# SCH_G-Cacher_2026-07-07.net
KiCad netlist of a schematic drawn in EasyEDA
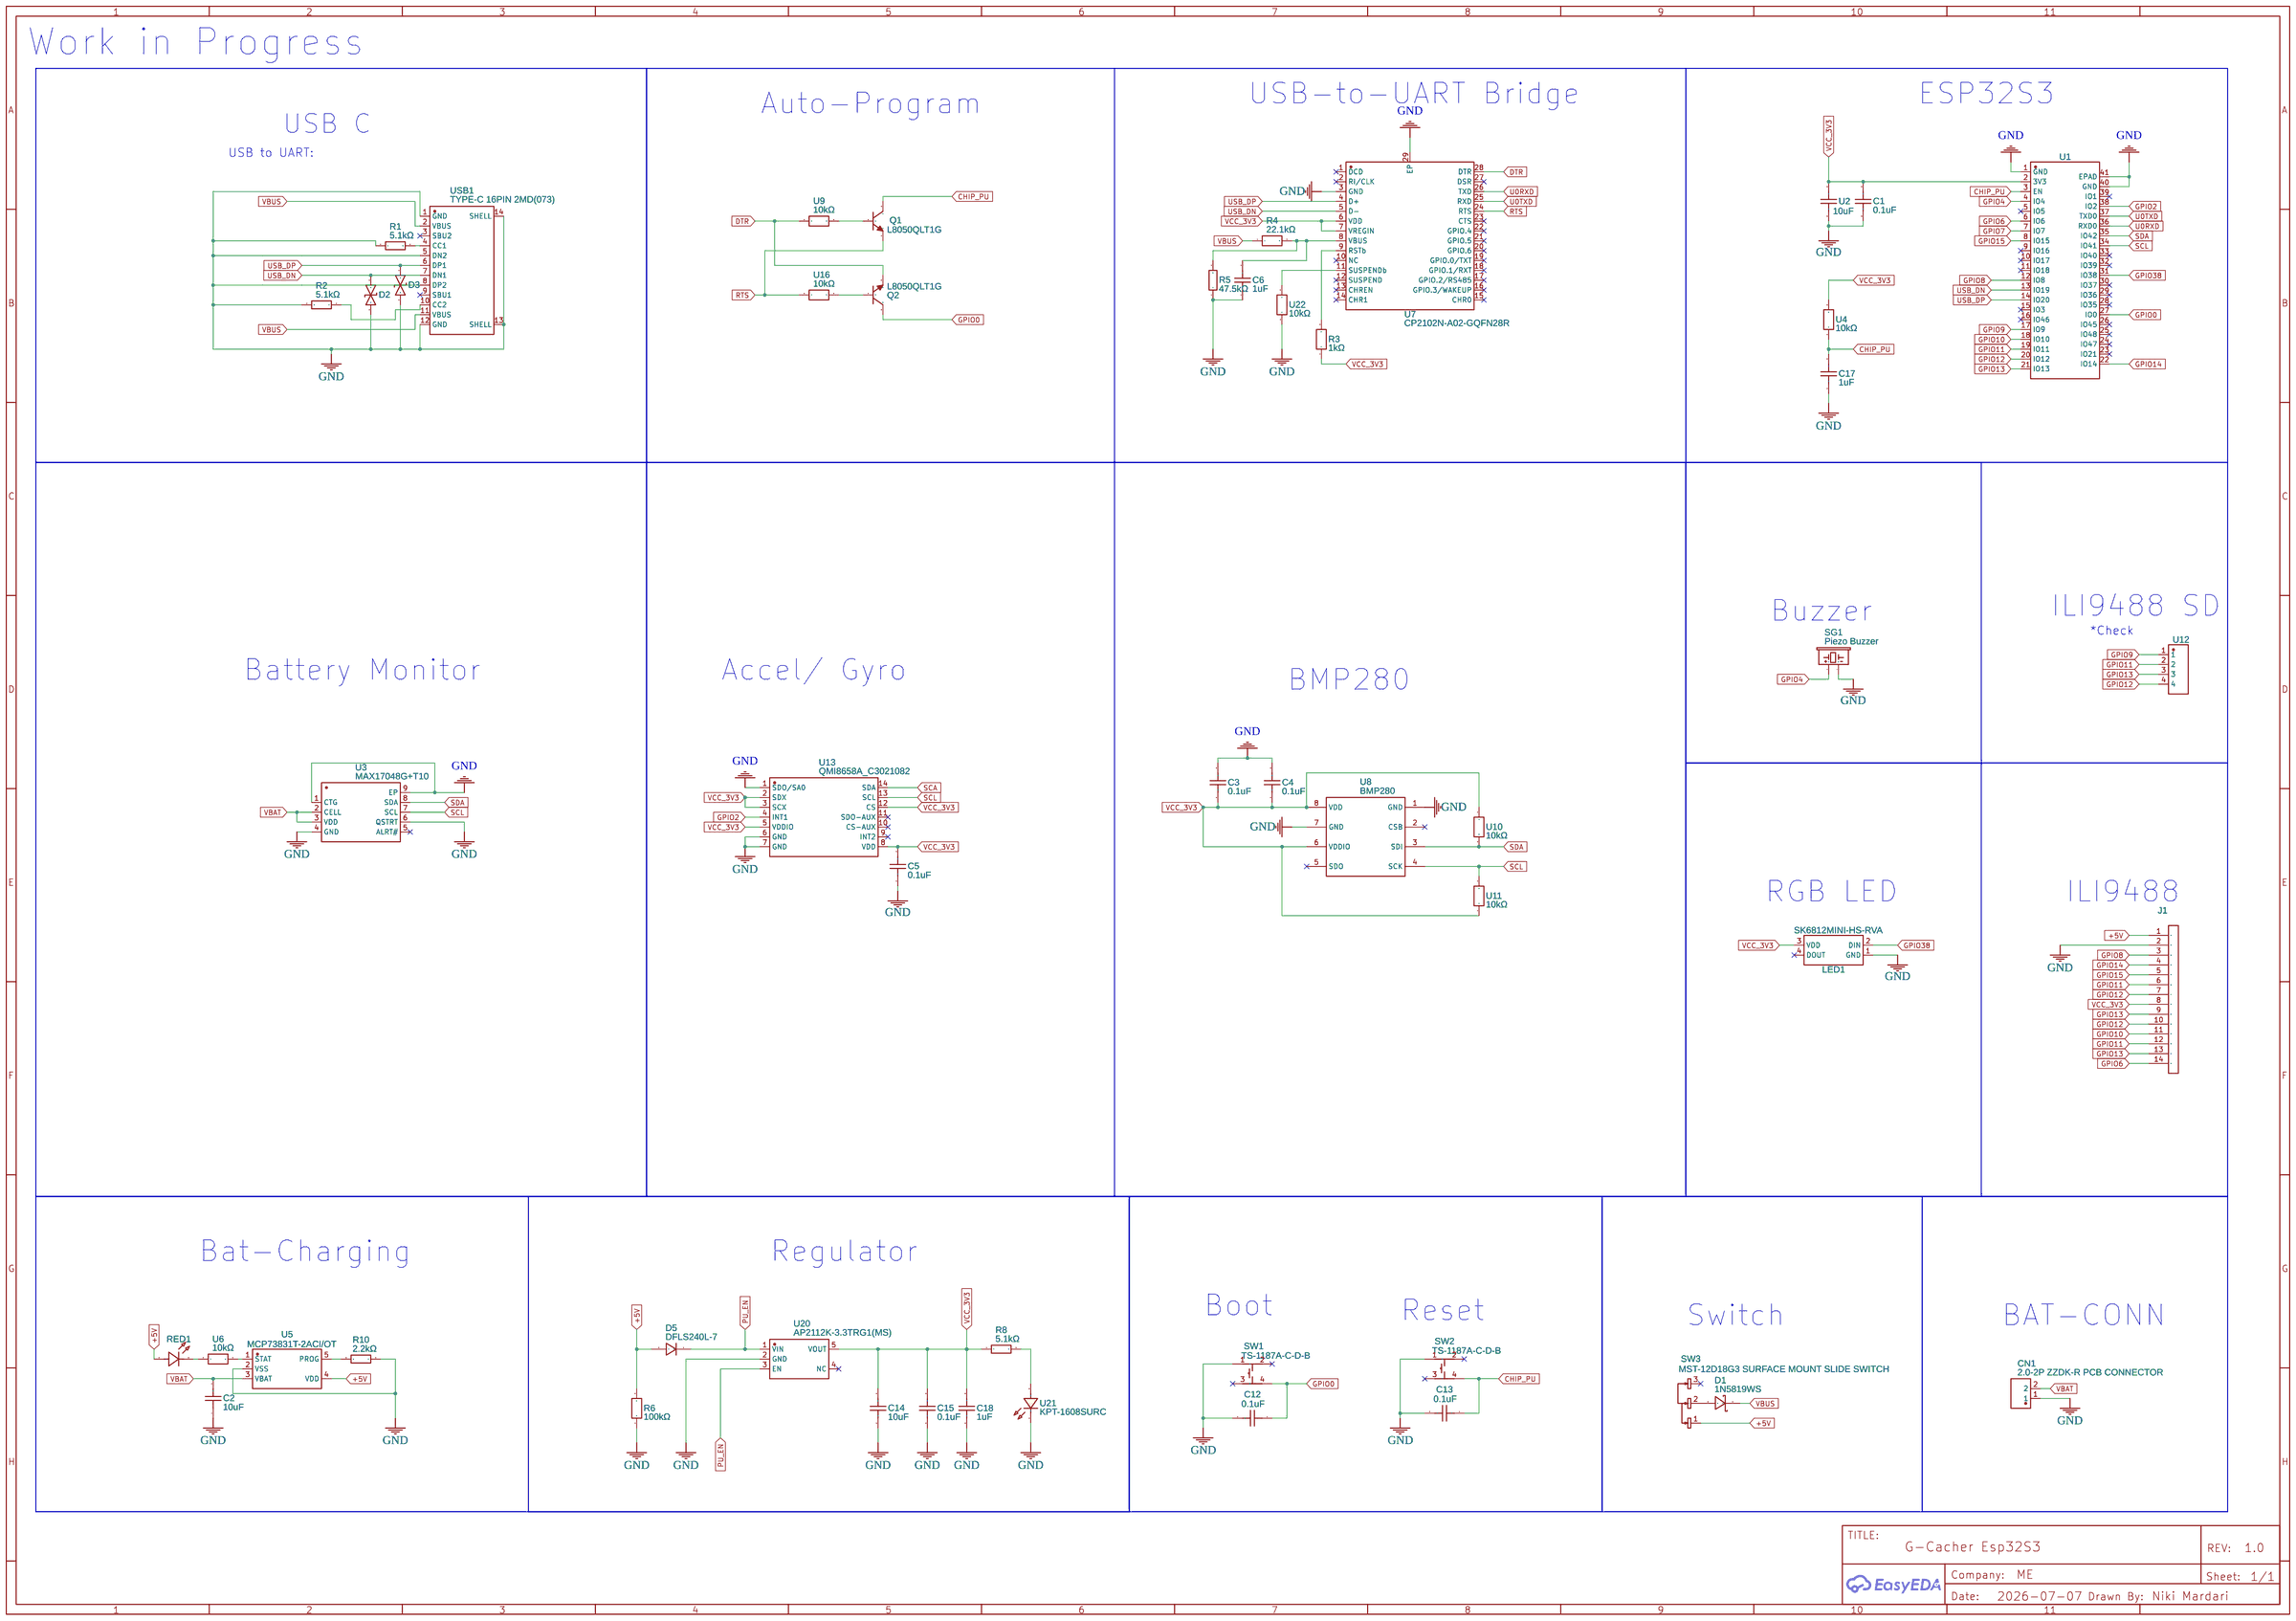
[diagram p0: schematic sheet]

(export (version "E")
  (design (tool "Eeschema 10.0.6"))
  (components
    (comp (ref "C1")
      (value "0.1uF")
      (fields (field (name "Manufacturer Part") "C1005X5R1E104M050BC") (field (name "Manufacturer") "TDK"))
      (libsource (lib "") (part "C1005X5R1E104M050BC_C3886291"))
    )
    (comp (ref "C2")
      (value "10uF")
      (fields (field (name "Manufacturer Part") "0603X106M100NT") (field (name "Manufacturer") "FH(风华)"))
      (libsource (lib "") (part "0603X106M100NT"))
    )
    (comp (ref "C3")
      (value "0.1uF")
      (fields (field (name "Manufacturer Part") "C1005X5R1E104M050BC") (field (name "Manufacturer") "TDK"))
      (libsource (lib "") (part "C1005X5R1E104M050BC_C3886291"))
    )
    (comp (ref "C4")
      (value "0.1uF")
      (fields (field (name "Manufacturer Part") "C1005X5R1E104M050BC") (field (name "Manufacturer") "TDK"))
      (libsource (lib "") (part "C1005X5R1E104M050BC_C3886291"))
    )
    (comp (ref "C5")
      (value "0.1uF")
      (fields (field (name "Manufacturer Part") "C1005X5R1E104M050BC") (field (name "Manufacturer") "TDK"))
      (libsource (lib "") (part "C1005X5R1E104M050BC_C3886291"))
    )
    (comp (ref "C6")
      (value "1uF")
      (fields (field (name "Manufacturer Part") "YNA18B3U0G105MT000N") (field (name "Manufacturer") "TDK"))
      (libsource (lib "") (part "YNA18B3U0G105MT000N"))
    )
    (comp (ref "C12")
      (value "0.1uF")
      (fields (field (name "Manufacturer Part") "C1005X5R1E104M050BC") (field (name "Manufacturer") "TDK"))
      (libsource (lib "") (part "C1005X5R1E104M050BC_C3886291_1"))
    )
    (comp (ref "C13")
      (value "0.1uF")
      (fields (field (name "Manufacturer Part") "C1005X5R1E104M050BC") (field (name "Manufacturer") "TDK"))
      (libsource (lib "") (part "C1005X5R1E104M050BC_C3886291_1"))
    )
    (comp (ref "C14")
      (value "10uF")
      (fields (field (name "Manufacturer Part") "0603X106M100NT") (field (name "Manufacturer") "FH(风华)"))
      (libsource (lib "") (part "0603X106M100NT"))
    )
    (comp (ref "C15")
      (value "0.1uF")
      (fields (field (name "Manufacturer Part") "C1005X5R1E104M050BC") (field (name "Manufacturer") "TDK"))
      (libsource (lib "") (part "C1005X5R1E104M050BC_C3886291"))
    )
    (comp (ref "C17")
      (value "1uF")
      (fields (field (name "Manufacturer Part") "YNA18B3U0G105MT000N") (field (name "Manufacturer") "TDK"))
      (libsource (lib "") (part "YNA18B3U0G105MT000N"))
    )
    (comp (ref "C18")
      (value "1uF")
      (fields (field (name "Manufacturer Part") "YNA18B3U0G105MT000N") (field (name "Manufacturer") "TDK"))
      (libsource (lib "") (part "YNA18B3U0G105MT000N"))
    )
    (comp (ref "CN1")
      (value "2.0-2P ZZDK-R PCB CONNECTOR")
      (fields
        (field (name "Manufacturer Part") "2.0-2P ZZDK-R PCB Connector")
        (field (name "Manufacturer") "SHOU HAN(首韩)")
      )
      (libsource (lib "") (part "2.0-2P ZZDK-R PCB CONNECTOR"))
    )
    (comp (ref "D1")
      (value "1N5819WS")
      (fields (field (name "Manufacturer") "Hottech(合科泰)"))
      (libsource (lib "") (part "1N5819WS"))
    )
    (comp (ref "D2")
      (value "LESD5D5.0CT1G")
      (fields (field (name "Manufacturer") "LRC(乐山无线电)"))
      (libsource (lib "") (part "LESD5D5.0CT1G"))
    )
    (comp (ref "D3")
      (value "LESD5D5.0CT1G")
      (fields (field (name "Manufacturer") "LRC(乐山无线电)"))
      (libsource (lib "") (part "LESD5D5.0CT1G"))
    )
    (comp (ref "D5")
      (value "DFLS240L-7")
      (fields (field (name "Manufacturer") "DIODES(美台)"))
      (libsource (lib "") (part "DFLS240L-7"))
    )
    (comp (ref "J1") (value "14 PIN FEMALE HEADER") (libsource (lib "") (part "14 PIN FEMALE HEADER")))
    (comp (ref "LED1")
      (value "SK6812MINI-HS-RVA")
      (fields (field (name "Manufacturer") "欧思科光电"))
      (libsource (lib "") (part "SK6812MINI-HS-RVA"))
    )
    (comp (ref "Q1")
      (value "L8050QLT1G")
      (fields (field (name "Manufacturer") "LRC(乐山无线电)"))
      (libsource (lib "") (part "L8050QLT1G"))
    )
    (comp (ref "Q2")
      (value "L8050QLT1G")
      (fields (field (name "Manufacturer") "LRC(乐山无线电)"))
      (libsource (lib "") (part "L8050QLT1G_1"))
    )
    (comp (ref "R1")
      (value "5.1kΩ")
      (fields
        (field (name "Manufacturer Part") "0402WGF5101TCE")
        (field (name "Manufacturer") "UNI-ROYAL(厚声)")
      )
      (libsource (lib "") (part "0402WGF5101TCE"))
    )
    (comp (ref "R2")
      (value "5.1kΩ")
      (fields
        (field (name "Manufacturer Part") "0402WGF5101TCE")
        (field (name "Manufacturer") "UNI-ROYAL(厚声)")
      )
      (libsource (lib "") (part "0402WGF5101TCE"))
    )
    (comp (ref "R3")
      (value "1kΩ")
      (fields (field (name "Manufacturer Part") "PTFR0603Q1K00N9") (field (name "Manufacturer") "RESI(开步睿思)"))
      (libsource (lib "") (part "PTFR0603Q1K00N9"))
    )
    (comp (ref "R4")
      (value "22.1kΩ")
      (fields (field (name "Manufacturer Part") "FRC0402F2212TS") (field (name "Manufacturer") "FOJAN(富捷)"))
      (libsource (lib "") (part "FRC0402F2212TS"))
    )
    (comp (ref "R5")
      (value "47.5kΩ")
      (fields (field (name "Manufacturer Part") "RC-02K4752FT") (field (name "Manufacturer") "FH(风华)"))
      (libsource (lib "") (part "RC-02K4752FT"))
    )
    (comp (ref "R6")
      (value "100kΩ")
      (fields
        (field (name "Manufacturer Part") "TR0603B100KP0525Z")
        (field (name "Manufacturer") "EVER OHMS(天二科技)")
      )
      (libsource (lib "") (part "TR0603B100KP0525Z"))
    )
    (comp (ref "R8")
      (value "5.1kΩ")
      (fields
        (field (name "Manufacturer Part") "0402WGF5101TCE")
        (field (name "Manufacturer") "UNI-ROYAL(厚声)")
      )
      (libsource (lib "") (part "0402WGF5101TCE"))
    )
    (comp (ref "R10")
      (value "2.2kΩ")
      (fields (field (name "Manufacturer Part") "RMC04022.2K5%N") (field (name "Manufacturer") "Tyohm(幸亚电阻)"))
      (libsource (lib "") (part "RMC04022.2K5%N"))
    )
    (comp (ref "RED1")
      (value "F.0603.00008/P2-0603R1TS2-06T-002")
      (fields (field (name "Manufacturer") "TUOZHAN(拓展光电)"))
      (libsource (lib "") (part "F.0603.00008/P2-0603R1TS2-06T-002"))
    )
    (comp (ref "SG1") (value "Piezo Buzzer") (libsource (lib "") (part "Piezo Buzzer")))
    (comp (ref "SW1")
      (value "TS-1187A-C-D-B")
      (fields (field (name "Manufacturer") "XKB Connection(中国星坤)"))
      (libsource (lib "") (part "TS-1187A-C-D-B"))
    )
    (comp (ref "SW2")
      (value "TS-1187A-C-D-B")
      (fields (field (name "Manufacturer") "XKB Connection(中国星坤)"))
      (libsource (lib "") (part "TS-1187A-C-D-B"))
    )
    (comp (ref "SW3")
      (value "MST-12D18G3 SURFACE MOUNT SLIDE SWITCH")
      (fields
        (field (name "Manufacturer Part") "MST-12D18G3 Surface Mount Slide Switch")
        (field (name "Manufacturer") "SHOU HAN(首韩)")
      )
      (libsource (lib "") (part "MST-12D18G3 SURFACE MOUNT SLIDE SWITCH"))
    )
    (comp (ref "U1") (value "ESPS3-32-WROOM-1-N16R8") (libsource (lib "") (part "ESPS3-32-WROOM-1-N16R8")))
    (comp (ref "U2")
      (value "10uF")
      (fields
        (field (name "Manufacturer Part") "HGC0603R5106K250NTHJ")
        (field (name "Manufacturer") "Chinocera(华瓷)")
      )
      (libsource (lib "") (part "HGC0603R5106K250NTHJ"))
    )
    (comp (ref "U3")
      (value "MAX17048G+T10")
      (fields (field (name "Manufacturer") "ADI(亚德诺)/MAXIM(美信)"))
      (libsource (lib "") (part "MAX17048G+T10"))
    )
    (comp (ref "U4")
      (value "10kΩ")
      (fields (field (name "Manufacturer Part") "THC02H1002BT") (field (name "Manufacturer") "FH(风华)"))
      (libsource (lib "") (part "THC02H1002BT"))
    )
    (comp (ref "U5")
      (value "MCP73831T-2ACI/OT")
      (fields (field (name "Manufacturer") "MICROCHIP(美国微芯)"))
      (libsource (lib "") (part "MCP73831T-2ACI/OT"))
    )
    (comp (ref "U6")
      (value "10kΩ")
      (fields
        (field (name "Manufacturer Part") "CRGH0603F10K")
        (field (name "Manufacturer") "TE Connectivity(泰科电子)")
      )
      (libsource (lib "") (part "CRGH0603F10K_1"))
    )
    (comp (ref "U7")
      (value "CP2102N-A02-GQFN28R")
      (fields (field (name "Manufacturer") "SKYWORKS/SILICON LABS(芯科)"))
      (libsource (lib "") (part "CP2102N-A02-GQFN28R"))
    )
    (comp (ref "U8")
      (value "BMP280")
      (fields (field (name "Manufacturer") "Bosch(博世)"))
      (libsource (lib "") (part "BMP280"))
    )
    (comp (ref "U9")
      (value "10kΩ")
      (fields
        (field (name "Manufacturer Part") "CRGH0603F10K")
        (field (name "Manufacturer") "TE Connectivity(泰科电子)")
      )
      (libsource (lib "") (part "CRGH0603F10K_2"))
    )
    (comp (ref "U10")
      (value "10kΩ")
      (fields
        (field (name "Manufacturer Part") "CRGH0603F10K")
        (field (name "Manufacturer") "TE Connectivity(泰科电子)")
      )
      (libsource (lib "") (part "CRGH0603F10K_3"))
    )
    (comp (ref "U11")
      (value "10kΩ")
      (fields
        (field (name "Manufacturer Part") "CRGH0603F10K")
        (field (name "Manufacturer") "TE Connectivity(泰科电子)")
      )
      (libsource (lib "") (part "CRGH0603F10K"))
    )
    (comp (ref "U12")
      (value "SSW-104-01-T-S")
      (fields (field (name "Manufacturer") "SAMTEC"))
      (libsource (lib "") (part "SSW-104-01-T-S"))
    )
    (comp (ref "U13")
      (value "QMI8658A_C3021082")
      (fields (field (name "Manufacturer Part") "QMI8658A") (field (name "Manufacturer") "QST(上海矽睿)"))
      (libsource (lib "") (part "QMI8658A_C3021082"))
    )
    (comp (ref "U16")
      (value "10kΩ")
      (fields
        (field (name "Manufacturer Part") "CRGH0603F10K")
        (field (name "Manufacturer") "TE Connectivity(泰科电子)")
      )
      (libsource (lib "") (part "CRGH0603F10K_2"))
    )
    (comp (ref "U20")
      (value "AP2112K-3.3TRG1(MS)")
      (fields (field (name "Manufacturer") "MSKSEMI(美森科)"))
      (libsource (lib "") (part "AP2112K-3.3TRG1(MS)"))
    )
    (comp (ref "U21")
      (value "KPT-1608SURC")
      (fields (field (name "Manufacturer") "Kingbright"))
      (libsource (lib "") (part "KPT-1608SURC"))
    )
    (comp (ref "U22")
      (value "10kΩ")
      (fields
        (field (name "Manufacturer Part") "CRGH0603F10K")
        (field (name "Manufacturer") "TE Connectivity(泰科电子)")
      )
      (libsource (lib "") (part "CRGH0603F10K"))
    )
    (comp (ref "USB1")
      (value "TYPE-C 16PIN 2MD(073)")
      (fields (field (name "Manufacturer") "SHOU HAN(首韩)"))
      (libsource (lib "") (part "TYPE-C 16PIN 2MD(073)"))
    )
  )
  (nets
    (net (code "1") (name "+5V") (class "Default")
      (node (ref "D5") (pin "2") (pinfunction "2_2") (pintype "unspecified"))
      (node (ref "J1") (pin "1") (pinfunction "1_1") (pintype "unspecified"))
      (node (ref "R6") (pin "2") (pinfunction "2_2") (pintype "unspecified"))
      (node (ref "RED1") (pin "1") (pinfunction "+_1") (pintype "unspecified"))
      (node (ref "SW3") (pin "1") (pinfunction "1_1") (pintype "unspecified"))
      (node (ref "U5") (pin "4") (pinfunction "VDD_4") (pintype "unspecified"))
    )
    (net (code "2") (name "CHIP_PU") (class "Default")
      (node (ref "C13") (pin "1") (pinfunction "1_1") (pintype "unspecified"))
      (node (ref "C17") (pin "2") (pinfunction "2_2") (pintype "unspecified"))
      (node (ref "Q1") (pin "3") (pinfunction "C_3") (pintype "unspecified"))
      (node (ref "SW2") (pin "4") (pinfunction "D_4") (pintype "unspecified"))
      (node (ref "U1") (pin "3") (pinfunction "EN_3") (pintype "unspecified"))
      (node (ref "U4") (pin "1") (pinfunction "1_1") (pintype "unspecified"))
    )
    (net (code "3") (name "DTR") (class "Default")
      (node (ref "Q2") (pin "2") (pinfunction "E_2") (pintype "unspecified"))
      (node (ref "U7") (pin "28") (pinfunction "DTR_28") (pintype "unspecified"))
      (node (ref "U9") (pin "1") (pinfunction "1_1") (pintype "unspecified"))
    )
    (net (code "4") (name "GND") (class "Default")
      (node (ref "C1") (pin "1") (pinfunction "1_1") (pintype "unspecified"))
      (node (ref "C12") (pin "2") (pinfunction "2_2") (pintype "unspecified"))
      (node (ref "C13") (pin "2") (pinfunction "2_2") (pintype "unspecified"))
      (node (ref "C14") (pin "1") (pinfunction "1_1") (pintype "unspecified"))
      (node (ref "C15") (pin "1") (pinfunction "1_1") (pintype "unspecified"))
      (node (ref "C17") (pin "1") (pinfunction "1_1") (pintype "unspecified"))
      (node (ref "C18") (pin "1") (pinfunction "1_1") (pintype "unspecified"))
      (node (ref "C2") (pin "1") (pinfunction "1_1") (pintype "unspecified"))
      (node (ref "C3") (pin "2") (pinfunction "2_2") (pintype "unspecified"))
      (node (ref "C4") (pin "2") (pinfunction "2_2") (pintype "unspecified"))
      (node (ref "C5") (pin "1") (pinfunction "1_1") (pintype "unspecified"))
      (node (ref "C6") (pin "1") (pinfunction "1_1") (pintype "unspecified"))
      (node (ref "CN1") (pin "1") (pinfunction "1_1") (pintype "unspecified"))
      (node (ref "D2") (pin "2") (pinfunction "2_2") (pintype "unspecified"))
      (node (ref "D3") (pin "2") (pinfunction "2_2") (pintype "unspecified"))
      (node (ref "J1") (pin "2") (pinfunction "2_2") (pintype "unspecified"))
      (node (ref "LED1") (pin "1") (pinfunction "GND_1") (pintype "unspecified"))
      (node (ref "R1") (pin "1") (pinfunction "1_1") (pintype "input"))
      (node (ref "R10") (pin "1") (pinfunction "1_1") (pintype "unspecified"))
      (node (ref "R2") (pin "1") (pinfunction "1_1") (pintype "input"))
      (node (ref "R5") (pin "1") (pinfunction "1_1") (pintype "unspecified"))
      (node (ref "R6") (pin "1") (pinfunction "1_1") (pintype "unspecified"))
      (node (ref "SG1") (pin "-") (pinfunction "2_-") (pintype "unspecified"))
      (node (ref "SW1") (pin "1") (pinfunction "A_1") (pintype "unspecified"))
      (node (ref "SW2") (pin "1") (pinfunction "A_1") (pintype "unspecified"))
      (node (ref "U1") (pin "1") (pinfunction "GND_1") (pintype "unspecified"))
      (node (ref "U1") (pin "40") (pinfunction "GND_40") (pintype "unspecified"))
      (node (ref "U1") (pin "41") (pinfunction "EPAD_41") (pintype "unspecified"))
      (node (ref "U13") (pin "1") (pinfunction "SDO/SA0_1") (pintype "unspecified"))
      (node (ref "U13") (pin "6") (pinfunction "GND_6") (pintype "unspecified"))
      (node (ref "U13") (pin "7") (pinfunction "GND_7") (pintype "unspecified"))
      (node (ref "U2") (pin "1") (pinfunction "1_1") (pintype "unspecified"))
      (node (ref "U20") (pin "2") (pinfunction "GND_2") (pintype "unspecified"))
      (node (ref "U21") (pin "1") (pinfunction "K_1") (pintype "unspecified"))
      (node (ref "U22") (pin "1") (pinfunction "1_1") (pintype "unspecified"))
      (node (ref "U3") (pin "1") (pinfunction "CTG_1") (pintype "unspecified"))
      (node (ref "U3") (pin "4") (pinfunction "GND_4") (pintype "unspecified"))
      (node (ref "U3") (pin "6") (pinfunction "QSTRT_6") (pintype "unspecified"))
      (node (ref "U3") (pin "9") (pinfunction "EP_9") (pintype "unspecified"))
      (node (ref "U5") (pin "2") (pinfunction "VSS_2") (pintype "unspecified"))
      (node (ref "U7") (pin "29") (pinfunction "EP_29") (pintype "unspecified"))
      (node (ref "U7") (pin "3") (pinfunction "GND_3") (pintype "unspecified"))
      (node (ref "U8") (pin "1") (pinfunction "GND_1") (pintype "unspecified"))
      (node (ref "U8") (pin "7") (pinfunction "GND_7") (pintype "unspecified"))
      (node (ref "USB1") (pin "1") (pinfunction "GND_1") (pintype "unspecified"))
      (node (ref "USB1") (pin "12") (pinfunction "GND_12") (pintype "unspecified"))
      (node (ref "USB1") (pin "13") (pinfunction "SHELL_13") (pintype "unspecified"))
      (node (ref "USB1") (pin "14") (pinfunction "SHELL_14") (pintype "unspecified"))
      (node (ref "USB1") (pin "5") (pinfunction "DN2_5") (pintype "unspecified"))
      (node (ref "USB1") (pin "8") (pinfunction "DP2_8") (pintype "unspecified"))
    )
    (net (code "5") (name "GPIO0") (class "Default")
      (node (ref "C12") (pin "1") (pinfunction "1_1") (pintype "unspecified"))
      (node (ref "Q2") (pin "3") (pinfunction "C_3") (pintype "unspecified"))
      (node (ref "SW1") (pin "4") (pinfunction "D_4") (pintype "unspecified"))
      (node (ref "U1") (pin "27") (pinfunction "IO0_27") (pintype "unspecified"))
    )
    (net (code "6") (name "GPIO2") (class "Default")
      (node (ref "U1") (pin "38") (pinfunction "IO2_38") (pintype "unspecified"))
      (node (ref "U13") (pin "4") (pinfunction "INT1_4") (pintype "unspecified"))
    )
    (net (code "7") (name "GPIO4") (class "Default")
      (node (ref "SG1") (pin "+") (pinfunction "1_+") (pintype "unspecified"))
      (node (ref "U1") (pin "4") (pinfunction "IO4_4") (pintype "unspecified"))
    )
    (net (code "8") (name "GPIO6") (class "Default")
      (node (ref "J1") (pin "14") (pinfunction "14_14") (pintype "unspecified"))
      (node (ref "U1") (pin "6") (pinfunction "IO6_6") (pintype "unspecified"))
    )
    (net (code "9") (name "GPIO7") (class "Default")
      (node (ref "U1") (pin "7") (pinfunction "IO7_7") (pintype "unspecified"))
    )
    (net (code "10") (name "GPIO8") (class "Default")
      (node (ref "J1") (pin "3") (pinfunction "3_3") (pintype "unspecified"))
      (node (ref "U1") (pin "12") (pinfunction "IO8_12") (pintype "unspecified"))
    )
    (net (code "11") (name "GPIO9") (class "Default")
      (node (ref "U1") (pin "17") (pinfunction "IO9_17") (pintype "unspecified"))
      (node (ref "U12") (pin "1") (pinfunction "1_1") (pintype "unspecified"))
    )
    (net (code "12") (name "GPIO10") (class "Default")
      (node (ref "J1") (pin "11") (pinfunction "11_11") (pintype "unspecified"))
      (node (ref "U1") (pin "18") (pinfunction "IO10_18") (pintype "unspecified"))
    )
    (net (code "13") (name "GPIO11") (class "Default")
      (node (ref "J1") (pin "12") (pinfunction "12_12") (pintype "unspecified"))
      (node (ref "J1") (pin "6") (pinfunction "6_6") (pintype "unspecified"))
      (node (ref "U1") (pin "19") (pinfunction "IO11_19") (pintype "unspecified"))
      (node (ref "U12") (pin "2") (pinfunction "2_2") (pintype "unspecified"))
    )
    (net (code "14") (name "GPIO12") (class "Default")
      (node (ref "J1") (pin "10") (pinfunction "10_10") (pintype "unspecified"))
      (node (ref "J1") (pin "7") (pinfunction "7_7") (pintype "unspecified"))
      (node (ref "U1") (pin "20") (pinfunction "IO12_20") (pintype "unspecified"))
      (node (ref "U12") (pin "4") (pinfunction "4_4") (pintype "unspecified"))
    )
    (net (code "15") (name "GPIO13") (class "Default")
      (node (ref "J1") (pin "13") (pinfunction "13_13") (pintype "unspecified"))
      (node (ref "J1") (pin "9") (pinfunction "9_9") (pintype "unspecified"))
      (node (ref "U1") (pin "21") (pinfunction "IO13_21") (pintype "unspecified"))
      (node (ref "U12") (pin "3") (pinfunction "3_3") (pintype "unspecified"))
    )
    (net (code "16") (name "GPIO14") (class "Default")
      (node (ref "J1") (pin "4") (pinfunction "4_4") (pintype "unspecified"))
      (node (ref "U1") (pin "22") (pinfunction "IO14_22") (pintype "unspecified"))
    )
    (net (code "17") (name "GPIO15") (class "Default")
      (node (ref "J1") (pin "5") (pinfunction "5_5") (pintype "unspecified"))
      (node (ref "U1") (pin "8") (pinfunction "IO15_8") (pintype "unspecified"))
    )
    (net (code "18") (name "GPIO38") (class "Default")
      (node (ref "LED1") (pin "2") (pinfunction "DIN_2") (pintype "unspecified"))
      (node (ref "U1") (pin "31") (pinfunction "IO38_31") (pintype "unspecified"))
    )
    (net (code "19") (name "Net-(D1-A)") (class "Default")
      (node (ref "D1") (pin "2") (pinfunction "A_2") (pintype "unspecified"))
      (node (ref "SW3") (pin "2") (pinfunction "2_2") (pintype "unspecified"))
    )
    (net (code "20") (name "Net-(Q1-B)") (class "Default")
      (node (ref "Q1") (pin "1") (pinfunction "B_1") (pintype "unspecified"))
      (node (ref "U9") (pin "2") (pinfunction "2_2") (pintype "unspecified"))
    )
    (net (code "21") (name "Net-(Q2-B)") (class "Default")
      (node (ref "Q2") (pin "1") (pinfunction "B_1") (pintype "unspecified"))
      (node (ref "U16") (pin "2") (pinfunction "2_2") (pintype "unspecified"))
    )
    (net (code "22") (name "Net-(RED1--)") (class "Default")
      (node (ref "RED1") (pin "2") (pinfunction "-_2") (pintype "unspecified"))
      (node (ref "U6") (pin "2") (pinfunction "2_2") (pintype "unspecified"))
    )
    (net (code "23") (name "Net-(U5-PROG)") (class "Default")
      (node (ref "R10") (pin "2") (pinfunction "2_2") (pintype "unspecified"))
      (node (ref "U5") (pin "5") (pinfunction "PROG_5") (pintype "unspecified"))
    )
    (net (code "24") (name "Net-(U5-STAT)") (class "Default")
      (node (ref "U5") (pin "1") (pinfunction "STAT_1") (pintype "unspecified"))
      (node (ref "U6") (pin "1") (pinfunction "1_1") (pintype "unspecified"))
    )
    (net (code "25") (name "Net-(U7-RSTb)") (class "Default")
      (node (ref "R3") (pin "2") (pinfunction "2_2") (pintype "unspecified"))
      (node (ref "U7") (pin "9") (pinfunction "RSTb_9") (pintype "unspecified"))
    )
    (net (code "26") (name "Net-(U7-SUSPENDb)") (class "Default")
      (node (ref "U22") (pin "2") (pinfunction "2_2") (pintype "unspecified"))
      (node (ref "U7") (pin "11") (pinfunction "SUSPENDb_11") (pintype "unspecified"))
    )
    (net (code "27") (name "Net-(U7-VBUS)") (class "Default")
      (node (ref "C6") (pin "2") (pinfunction "2_2") (pintype "unspecified"))
      (node (ref "R4") (pin "2") (pinfunction "2_2") (pintype "unspecified"))
      (node (ref "R5") (pin "2") (pinfunction "2_2") (pintype "unspecified"))
      (node (ref "U7") (pin "8") (pinfunction "VBUS_8") (pintype "unspecified"))
    )
    (net (code "28") (name "Net-(U21-A)") (class "Default")
      (node (ref "R8") (pin "2") (pinfunction "2_2") (pintype "input"))
      (node (ref "U21") (pin "2") (pinfunction "A_2") (pintype "unspecified"))
    )
    (net (code "29") (name "Net-(USB1-CC1)") (class "Default")
      (node (ref "R1") (pin "2") (pinfunction "2_2") (pintype "input"))
      (node (ref "USB1") (pin "4") (pinfunction "CC1_4") (pintype "unspecified"))
    )
    (net (code "30") (name "Net-(USB1-CC2)") (class "Default")
      (node (ref "R2") (pin "2") (pinfunction "2_2") (pintype "input"))
      (node (ref "USB1") (pin "10") (pinfunction "CC2_10") (pintype "unspecified"))
    )
    (net (code "31") (name "PU_EN") (class "Default")
      (node (ref "D5") (pin "1") (pinfunction "1_1") (pintype "unspecified"))
      (node (ref "U20") (pin "1") (pinfunction "VIN_1") (pintype "unspecified"))
      (node (ref "U20") (pin "3") (pinfunction "EN_3") (pintype "unspecified"))
    )
    (net (code "32") (name "RTS") (class "Default")
      (node (ref "Q1") (pin "2") (pinfunction "E_2") (pintype "unspecified"))
      (node (ref "U16") (pin "1") (pinfunction "1_1") (pintype "unspecified"))
      (node (ref "U7") (pin "24") (pinfunction "RTS_24") (pintype "unspecified"))
    )
    (net (code "33") (name "SCA") (class "Default")
      (node (ref "U13") (pin "14") (pinfunction "SDA_14") (pintype "unspecified"))
    )
    (net (code "34") (name "SCL") (class "Default")
      (node (ref "U1") (pin "34") (pinfunction "IO41_34") (pintype "unspecified"))
      (node (ref "U11") (pin "2") (pinfunction "2_2") (pintype "unspecified"))
      (node (ref "U13") (pin "13") (pinfunction "SCL_13") (pintype "unspecified"))
      (node (ref "U3") (pin "7") (pinfunction "SCL_7") (pintype "unspecified"))
      (node (ref "U8") (pin "4") (pinfunction "SCK_4") (pintype "unspecified"))
    )
    (net (code "35") (name "SDA") (class "Default")
      (node (ref "U1") (pin "35") (pinfunction "IO42_35") (pintype "unspecified"))
      (node (ref "U10") (pin "2") (pinfunction "2_2") (pintype "unspecified"))
      (node (ref "U3") (pin "8") (pinfunction "SDA_8") (pintype "unspecified"))
      (node (ref "U8") (pin "3") (pinfunction "SDI_3") (pintype "unspecified"))
    )
    (net (code "36") (name "U0RXD") (class "Default")
      (node (ref "U1") (pin "36") (pinfunction "RXD0_36") (pintype "unspecified"))
      (node (ref "U7") (pin "26") (pinfunction "TXD_26") (pintype "unspecified"))
    )
    (net (code "37") (name "U0TXD") (class "Default")
      (node (ref "U1") (pin "37") (pinfunction "TXD0_37") (pintype "unspecified"))
      (node (ref "U7") (pin "25") (pinfunction "RXD_25") (pintype "unspecified"))
    )
    (net (code "38") (name "USB_DN") (class "Default")
      (node (ref "D2") (pin "1") (pinfunction "1_1") (pintype "unspecified"))
      (node (ref "U1") (pin "13") (pinfunction "IO19_13") (pintype "unspecified"))
      (node (ref "U7") (pin "5") (pinfunction "D-_5") (pintype "unspecified"))
      (node (ref "USB1") (pin "7") (pinfunction "DN1_7") (pintype "unspecified"))
    )
    (net (code "39") (name "USB_DP") (class "Default")
      (node (ref "D3") (pin "1") (pinfunction "1_1") (pintype "unspecified"))
      (node (ref "U1") (pin "14") (pinfunction "IO20_14") (pintype "unspecified"))
      (node (ref "U7") (pin "4") (pinfunction "D+_4") (pintype "unspecified"))
      (node (ref "USB1") (pin "6") (pinfunction "DP1_6") (pintype "unspecified"))
    )
    (net (code "40") (name "VBAT") (class "Default")
      (node (ref "C2") (pin "2") (pinfunction "2_2") (pintype "unspecified"))
      (node (ref "CN1") (pin "2") (pinfunction "2_2") (pintype "unspecified"))
      (node (ref "U3") (pin "2") (pinfunction "CELL_2") (pintype "unspecified"))
      (node (ref "U3") (pin "3") (pinfunction "VDD_3") (pintype "unspecified"))
      (node (ref "U5") (pin "3") (pinfunction "VBAT_3") (pintype "unspecified"))
    )
    (net (code "41") (name "VBUS") (class "Default")
      (node (ref "D1") (pin "1") (pinfunction "K_1") (pintype "unspecified"))
      (node (ref "R4") (pin "1") (pinfunction "1_1") (pintype "unspecified"))
      (node (ref "USB1") (pin "11") (pinfunction "VBUS_11") (pintype "unspecified"))
      (node (ref "USB1") (pin "2") (pinfunction "VBUS_2") (pintype "unspecified"))
    )
    (net (code "42") (name "VCC_3V3") (class "Default")
      (node (ref "C1") (pin "2") (pinfunction "2_2") (pintype "unspecified"))
      (node (ref "C14") (pin "2") (pinfunction "2_2") (pintype "unspecified"))
      (node (ref "C15") (pin "2") (pinfunction "2_2") (pintype "unspecified"))
      (node (ref "C18") (pin "2") (pinfunction "2_2") (pintype "unspecified"))
      (node (ref "C3") (pin "1") (pinfunction "1_1") (pintype "unspecified"))
      (node (ref "C4") (pin "1") (pinfunction "1_1") (pintype "unspecified"))
      (node (ref "C5") (pin "2") (pinfunction "2_2") (pintype "unspecified"))
      (node (ref "J1") (pin "8") (pinfunction "8_8") (pintype "unspecified"))
      (node (ref "LED1") (pin "3") (pinfunction "VDD_3") (pintype "unspecified"))
      (node (ref "R3") (pin "1") (pinfunction "1_1") (pintype "unspecified"))
      (node (ref "R8") (pin "1") (pinfunction "1_1") (pintype "input"))
      (node (ref "U1") (pin "2") (pinfunction "3V3_2") (pintype "unspecified"))
      (node (ref "U10") (pin "1") (pinfunction "1_1") (pintype "unspecified"))
      (node (ref "U11") (pin "1") (pinfunction "1_1") (pintype "unspecified"))
      (node (ref "U13") (pin "12") (pinfunction "CS_12") (pintype "unspecified"))
      (node (ref "U13") (pin "2") (pinfunction "SDX_2") (pintype "unspecified"))
      (node (ref "U13") (pin "3") (pinfunction "SCX_3") (pintype "unspecified"))
      (node (ref "U13") (pin "5") (pinfunction "VDDIO_5") (pintype "unspecified"))
      (node (ref "U13") (pin "8") (pinfunction "VDD_8") (pintype "unspecified"))
      (node (ref "U2") (pin "2") (pinfunction "2_2") (pintype "unspecified"))
      (node (ref "U20") (pin "5") (pinfunction "VOUT_5") (pintype "unspecified"))
      (node (ref "U4") (pin "2") (pinfunction "2_2") (pintype "unspecified"))
      (node (ref "U7") (pin "6") (pinfunction "VDD_6") (pintype "unspecified"))
      (node (ref "U7") (pin "7") (pinfunction "VREGIN_7") (pintype "unspecified"))
      (node (ref "U8") (pin "6") (pinfunction "VDDIO_6") (pintype "unspecified"))
      (node (ref "U8") (pin "8") (pinfunction "VDD_8") (pintype "unspecified"))
    )
    (net (code "43") (name "unconnected-(LED1-DOUT-Pad4)") (class "Default")
      (node (ref "LED1") (pin "4") (pinfunction "DOUT_4") (pintype "unspecified+no_connect"))
    )
    (net (code "44") (name "unconnected-(SW1-B-Pad2)") (class "Default")
      (node (ref "SW1") (pin "2") (pinfunction "B_2") (pintype "unspecified+no_connect"))
    )
    (net (code "45") (name "unconnected-(SW1-C-Pad3)") (class "Default")
      (node (ref "SW1") (pin "3") (pinfunction "C_3") (pintype "unspecified+no_connect"))
    )
    (net (code "46") (name "unconnected-(SW2-B-Pad2)") (class "Default")
      (node (ref "SW2") (pin "2") (pinfunction "B_2") (pintype "unspecified+no_connect"))
    )
    (net (code "47") (name "unconnected-(SW2-C-Pad3)") (class "Default")
      (node (ref "SW2") (pin "3") (pinfunction "C_3") (pintype "unspecified+no_connect"))
    )
    (net (code "48") (name "unconnected-(SW3-Pad3)") (class "Default")
      (node (ref "SW3") (pin "3") (pinfunction "3_3") (pintype "unspecified+no_connect"))
    )
    (net (code "49") (name "unconnected-(U1-IO1-Pad39)") (class "Default")
      (node (ref "U1") (pin "39") (pinfunction "IO1_39") (pintype "unspecified+no_connect"))
    )
    (net (code "50") (name "unconnected-(U1-IO3-Pad15)") (class "Default")
      (node (ref "U1") (pin "15") (pinfunction "IO3_15") (pintype "unspecified+no_connect"))
    )
    (net (code "51") (name "unconnected-(U1-IO5-Pad5)") (class "Default")
      (node (ref "U1") (pin "5") (pinfunction "IO5_5") (pintype "unspecified+no_connect"))
    )
    (net (code "52") (name "unconnected-(U1-IO16-Pad9)") (class "Default")
      (node (ref "U1") (pin "9") (pinfunction "IO16_9") (pintype "unspecified+no_connect"))
    )
    (net (code "53") (name "unconnected-(U1-IO17-Pad10)") (class "Default")
      (node (ref "U1") (pin "10") (pinfunction "IO17_10") (pintype "unspecified+no_connect"))
    )
    (net (code "54") (name "unconnected-(U1-IO18-Pad11)") (class "Default")
      (node (ref "U1") (pin "11") (pinfunction "IO18_11") (pintype "unspecified+no_connect"))
    )
    (net (code "55") (name "unconnected-(U1-IO21-Pad23)") (class "Default")
      (node (ref "U1") (pin "23") (pinfunction "IO21_23") (pintype "unspecified+no_connect"))
    )
    (net (code "56") (name "unconnected-(U1-IO35-Pad28)") (class "Default")
      (node (ref "U1") (pin "28") (pinfunction "IO35_28") (pintype "unspecified+no_connect"))
    )
    (net (code "57") (name "unconnected-(U1-IO36-Pad29)") (class "Default")
      (node (ref "U1") (pin "29") (pinfunction "IO36_29") (pintype "unspecified+no_connect"))
    )
    (net (code "58") (name "unconnected-(U1-IO37-Pad30)") (class "Default")
      (node (ref "U1") (pin "30") (pinfunction "IO37_30") (pintype "unspecified+no_connect"))
    )
    (net (code "59") (name "unconnected-(U1-IO39-Pad32)") (class "Default")
      (node (ref "U1") (pin "32") (pinfunction "IO39_32") (pintype "unspecified+no_connect"))
    )
    (net (code "60") (name "unconnected-(U1-IO40-Pad33)") (class "Default")
      (node (ref "U1") (pin "33") (pinfunction "IO40_33") (pintype "unspecified+no_connect"))
    )
    (net (code "61") (name "unconnected-(U1-IO45-Pad26)") (class "Default")
      (node (ref "U1") (pin "26") (pinfunction "IO45_26") (pintype "unspecified+no_connect"))
    )
    (net (code "62") (name "unconnected-(U1-IO46-Pad16)") (class "Default")
      (node (ref "U1") (pin "16") (pinfunction "IO46_16") (pintype "unspecified+no_connect"))
    )
    (net (code "63") (name "unconnected-(U1-IO47-Pad24)") (class "Default")
      (node (ref "U1") (pin "24") (pinfunction "IO47_24") (pintype "unspecified+no_connect"))
    )
    (net (code "64") (name "unconnected-(U1-IO48-Pad25)") (class "Default")
      (node (ref "U1") (pin "25") (pinfunction "IO48_25") (pintype "unspecified+no_connect"))
    )
    (net (code "65") (name "unconnected-(U3-ALRT#-Pad5)") (class "Default")
      (node (ref "U3") (pin "5") (pinfunction "ALRT#_5") (pintype "unspecified+no_connect"))
    )
    (net (code "66") (name "unconnected-(U7-CHR0-Pad15)") (class "Default")
      (node (ref "U7") (pin "15") (pinfunction "CHR0_15") (pintype "unspecified+no_connect"))
    )
    (net (code "67") (name "unconnected-(U7-CHR1-Pad14)") (class "Default")
      (node (ref "U7") (pin "14") (pinfunction "CHR1_14") (pintype "unspecified+no_connect"))
    )
    (net (code "68") (name "unconnected-(U7-CHREN-Pad13)") (class "Default")
      (node (ref "U7") (pin "13") (pinfunction "CHREN_13") (pintype "unspecified+no_connect"))
    )
    (net (code "69") (name "unconnected-(U7-CTS-Pad23)") (class "Default")
      (node (ref "U7") (pin "23") (pinfunction "CTS_23") (pintype "unspecified+no_connect"))
    )
    (net (code "70") (name "unconnected-(U7-DCD-Pad1)") (class "Default")
      (node (ref "U7") (pin "1") (pinfunction "DCD_1") (pintype "unspecified+no_connect"))
    )
    (net (code "71") (name "unconnected-(U7-DSR-Pad27)") (class "Default")
      (node (ref "U7") (pin "27") (pinfunction "DSR_27") (pintype "unspecified+no_connect"))
    )
    (net (code "72") (name "unconnected-(U7-GPIO.0{slash}TXT-Pad19)") (class "Default")
      (node (ref "U7") (pin "19") (pinfunction "GPIO.0/TXT_19") (pintype "unspecified+no_connect"))
    )
    (net (code "73") (name "unconnected-(U7-GPIO.1{slash}RXT-Pad18)") (class "Default")
      (node (ref "U7") (pin "18") (pinfunction "GPIO.1/RXT_18") (pintype "unspecified+no_connect"))
    )
    (net (code "74") (name "unconnected-(U7-GPIO.2{slash}RS485-Pad17)") (class "Default")
      (node (ref "U7") (pin "17") (pinfunction "GPIO.2/RS485_17") (pintype "unspecified+no_connect"))
    )
    (net (code "75") (name "unconnected-(U7-GPIO.3{slash}WAKEUP-Pad16)") (class "Default")
      (node (ref "U7") (pin "16") (pinfunction "GPIO.3/WAKEUP_16") (pintype "unspecified+no_connect"))
    )
    (net (code "76") (name "unconnected-(U7-GPIO.4-Pad22)") (class "Default")
      (node (ref "U7") (pin "22") (pinfunction "GPIO.4_22") (pintype "unspecified+no_connect"))
    )
    (net (code "77") (name "unconnected-(U7-GPIO.5-Pad21)") (class "Default")
      (node (ref "U7") (pin "21") (pinfunction "GPIO.5_21") (pintype "unspecified+no_connect"))
    )
    (net (code "78") (name "unconnected-(U7-GPIO.6-Pad20)") (class "Default")
      (node (ref "U7") (pin "20") (pinfunction "GPIO.6_20") (pintype "unspecified+no_connect"))
    )
    (net (code "79") (name "unconnected-(U7-NC-Pad10)") (class "Default")
      (node (ref "U7") (pin "10") (pinfunction "NC_10") (pintype "unspecified+no_connect"))
    )
    (net (code "80") (name "unconnected-(U7-RI{slash}CLK-Pad2)") (class "Default")
      (node (ref "U7") (pin "2") (pinfunction "RI/CLK_2") (pintype "unspecified+no_connect"))
    )
    (net (code "81") (name "unconnected-(U7-SUSPEND-Pad12)") (class "Default")
      (node (ref "U7") (pin "12") (pinfunction "SUSPEND_12") (pintype "unspecified+no_connect"))
    )
    (net (code "82") (name "unconnected-(U8-CSB-Pad2)") (class "Default")
      (node (ref "U8") (pin "2") (pinfunction "CSB_2") (pintype "unspecified+no_connect"))
    )
    (net (code "83") (name "unconnected-(U8-SDO-Pad5)") (class "Default")
      (node (ref "U8") (pin "5") (pinfunction "SDO_5") (pintype "unspecified+no_connect"))
    )
    (net (code "84") (name "unconnected-(U13-CS-AUX-Pad10)") (class "Default")
      (node (ref "U13") (pin "10") (pinfunction "CS-AUX_10") (pintype "unspecified+no_connect"))
    )
    (net (code "85") (name "unconnected-(U13-INT2-Pad9)") (class "Default")
      (node (ref "U13") (pin "9") (pinfunction "INT2_9") (pintype "unspecified+no_connect"))
    )
    (net (code "86") (name "unconnected-(U13-SDO-AUX-Pad11)") (class "Default")
      (node (ref "U13") (pin "11") (pinfunction "SDO-AUX_11") (pintype "unspecified+no_connect"))
    )
    (net (code "87") (name "unconnected-(U20-NC-Pad4)") (class "Default")
      (node (ref "U20") (pin "4") (pinfunction "NC_4") (pintype "unspecified+no_connect"))
    )
    (net (code "88") (name "unconnected-(USB1-SBU1-Pad9)") (class "Default")
      (node (ref "USB1") (pin "9") (pinfunction "SBU1_9") (pintype "unspecified+no_connect"))
    )
    (net (code "89") (name "unconnected-(USB1-SBU2-Pad3)") (class "Default")
      (node (ref "USB1") (pin "3") (pinfunction "SBU2_3") (pintype "unspecified+no_connect"))
    )
  )
)
